# serial.net
KiCad netlist of a schematic drawn in EAGLE
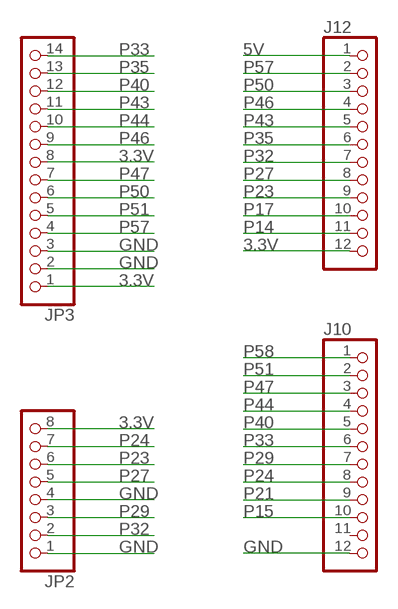
[diagram p0: schematic, sheet 1]

(export (version "E")
  (design (tool "Eeschema 10.0.6"))
  (components
    (comp (ref "J10")
      (value "PINHD-1X12")
      (footprint "eagle-import:1X12")
      (libsource (lib "eagle-import") (part "PINHD-1X12"))
    )
    (comp (ref "J12")
      (value "PINHD-1X12")
      (footprint "eagle-import:1X12")
      (libsource (lib "eagle-import") (part "PINHD-1X12"))
    )
    (comp (ref "JP2")
      (value "PINHD-1X8")
      (footprint "eagle-import:1X08")
      (libsource (lib "eagle-import") (part "PINHD-1X8"))
    )
    (comp (ref "JP3")
      (value "PINHD-1X14")
      (footprint "eagle-import:1X14")
      (libsource (lib "eagle-import") (part "PINHD-1X14"))
    )
  )
  (nets
    (net (code "1") (name "/3.3V") (class "Default")
      (node (ref "J12") (pin "12") (pinfunction "12_12") (pintype "passive"))
      (node (ref "JP2") (pin "8") (pinfunction "8_8") (pintype "passive"))
      (node (ref "JP3") (pin "1") (pinfunction "1_1") (pintype "passive"))
      (node (ref "JP3") (pin "8") (pinfunction "8_8") (pintype "passive"))
    )
    (net (code "2") (name "/5V") (class "Default")
      (node (ref "J12") (pin "1") (pinfunction "1_1") (pintype "passive"))
    )
    (net (code "3") (name "/GND") (class "Default")
      (node (ref "J10") (pin "12") (pinfunction "12_12") (pintype "passive"))
      (node (ref "JP2") (pin "1") (pinfunction "1_1") (pintype "passive"))
      (node (ref "JP2") (pin "4") (pinfunction "4_4") (pintype "passive"))
      (node (ref "JP3") (pin "2") (pinfunction "2_2") (pintype "passive"))
      (node (ref "JP3") (pin "3") (pinfunction "3_3") (pintype "passive"))
    )
    (net (code "4") (name "/P14") (class "Default")
      (node (ref "J12") (pin "11") (pinfunction "11_11") (pintype "passive"))
    )
    (net (code "5") (name "/P15") (class "Default")
      (node (ref "J10") (pin "10") (pinfunction "10_10") (pintype "passive"))
    )
    (net (code "6") (name "/P17") (class "Default")
      (node (ref "J12") (pin "10") (pinfunction "10_10") (pintype "passive"))
    )
    (net (code "7") (name "/P21") (class "Default")
      (node (ref "J10") (pin "9") (pinfunction "9_9") (pintype "passive"))
    )
    (net (code "8") (name "/P23") (class "Default")
      (node (ref "J12") (pin "9") (pinfunction "9_9") (pintype "passive"))
      (node (ref "JP2") (pin "6") (pinfunction "6_6") (pintype "passive"))
    )
    (net (code "9") (name "/P24") (class "Default")
      (node (ref "J10") (pin "8") (pinfunction "8_8") (pintype "passive"))
      (node (ref "JP2") (pin "7") (pinfunction "7_7") (pintype "passive"))
    )
    (net (code "10") (name "/P27") (class "Default")
      (node (ref "J12") (pin "8") (pinfunction "8_8") (pintype "passive"))
      (node (ref "JP2") (pin "5") (pinfunction "5_5") (pintype "passive"))
    )
    (net (code "11") (name "/P29") (class "Default")
      (node (ref "J10") (pin "7") (pinfunction "7_7") (pintype "passive"))
      (node (ref "JP2") (pin "3") (pinfunction "3_3") (pintype "passive"))
    )
    (net (code "12") (name "/P32") (class "Default")
      (node (ref "J12") (pin "7") (pinfunction "7_7") (pintype "passive"))
      (node (ref "JP2") (pin "2") (pinfunction "2_2") (pintype "passive"))
    )
    (net (code "13") (name "/P33") (class "Default")
      (node (ref "J10") (pin "6") (pinfunction "6_6") (pintype "passive"))
      (node (ref "JP3") (pin "14") (pinfunction "14_14") (pintype "passive"))
    )
    (net (code "14") (name "/P35") (class "Default")
      (node (ref "J12") (pin "6") (pinfunction "6_6") (pintype "passive"))
      (node (ref "JP3") (pin "13") (pinfunction "13_13") (pintype "passive"))
    )
    (net (code "15") (name "/P40") (class "Default")
      (node (ref "J10") (pin "5") (pinfunction "5_5") (pintype "passive"))
      (node (ref "JP3") (pin "12") (pinfunction "12_12") (pintype "passive"))
    )
    (net (code "16") (name "/P43") (class "Default")
      (node (ref "J12") (pin "5") (pinfunction "5_5") (pintype "passive"))
      (node (ref "JP3") (pin "11") (pinfunction "11_11") (pintype "passive"))
    )
    (net (code "17") (name "/P44") (class "Default")
      (node (ref "J10") (pin "4") (pinfunction "4_4") (pintype "passive"))
      (node (ref "JP3") (pin "10") (pinfunction "10_10") (pintype "passive"))
    )
    (net (code "18") (name "/P46") (class "Default")
      (node (ref "J12") (pin "4") (pinfunction "4_4") (pintype "passive"))
      (node (ref "JP3") (pin "9") (pinfunction "9_9") (pintype "passive"))
    )
    (net (code "19") (name "/P47") (class "Default")
      (node (ref "J10") (pin "3") (pinfunction "3_3") (pintype "passive"))
      (node (ref "JP3") (pin "7") (pinfunction "7_7") (pintype "passive"))
    )
    (net (code "20") (name "/P50") (class "Default")
      (node (ref "J12") (pin "3") (pinfunction "3_3") (pintype "passive"))
      (node (ref "JP3") (pin "6") (pinfunction "6_6") (pintype "passive"))
    )
    (net (code "21") (name "/P51") (class "Default")
      (node (ref "J10") (pin "2") (pinfunction "2_2") (pintype "passive"))
      (node (ref "JP3") (pin "5") (pinfunction "5_5") (pintype "passive"))
    )
    (net (code "22") (name "/P57") (class "Default")
      (node (ref "J12") (pin "2") (pinfunction "2_2") (pintype "passive"))
      (node (ref "JP3") (pin "4") (pinfunction "4_4") (pintype "passive"))
    )
    (net (code "23") (name "/P58") (class "Default")
      (node (ref "J10") (pin "1") (pinfunction "1_1") (pintype "passive"))
    )
    (net (code "24") (name "unconnected-(J10-Pad11)") (class "Default")
      (node (ref "J10") (pin "11") (pinfunction "11_11") (pintype "passive"))
    )
  )
)
